# PG03_SHEET1.net
KiCad netlist of a schematic drawn in Altium Designer
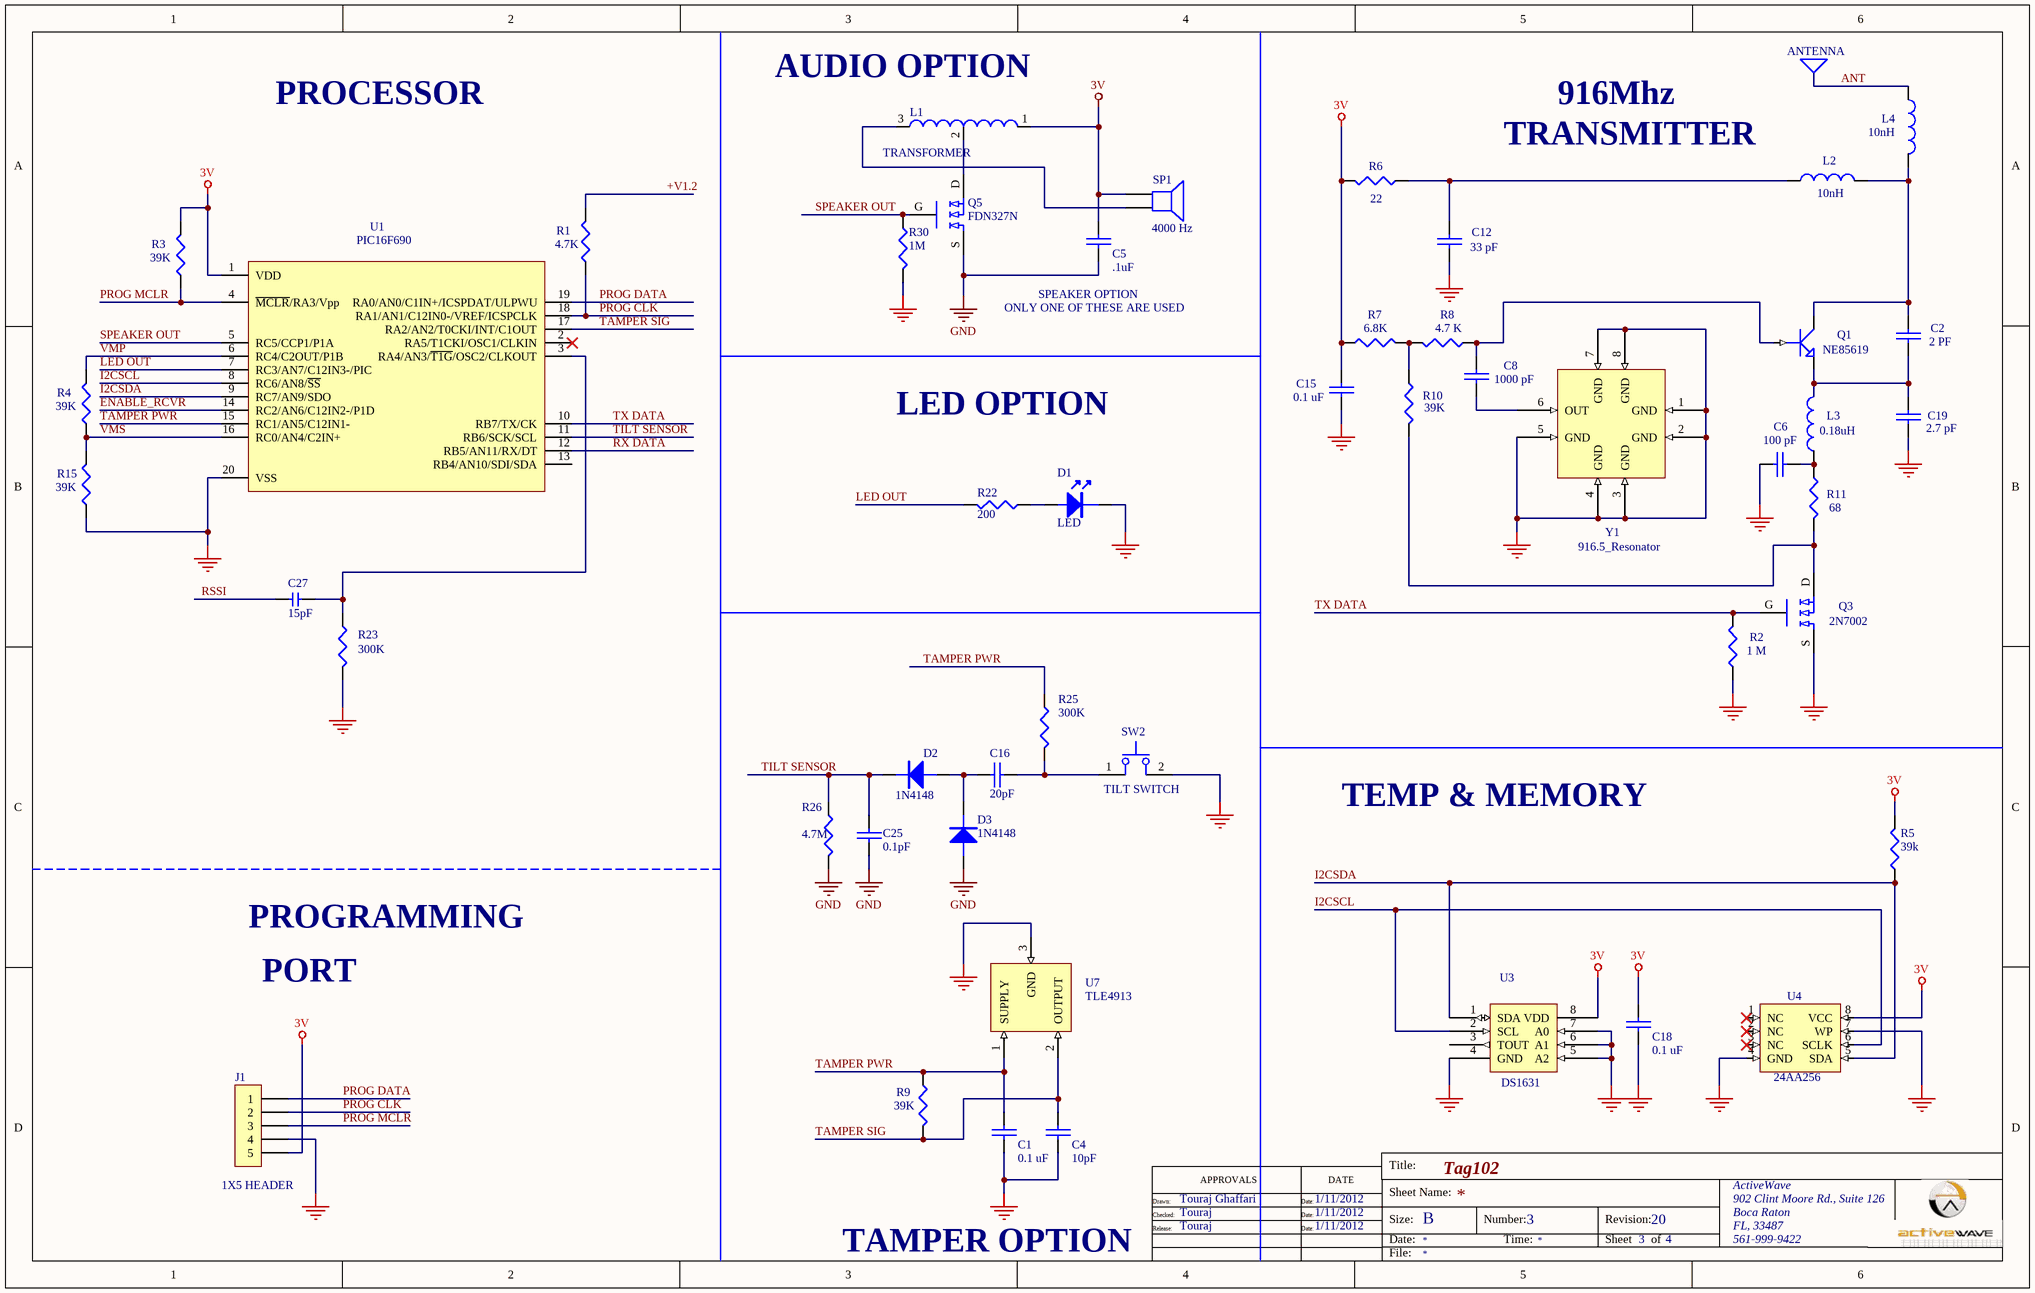
[diagram p0: PG03 SHEET1.schdoc]

(export (version "E")
  (design (tool "Eeschema 10.0.6"))
  (components
    (comp (ref "C1")
      (value "0.1 uF")
      (footprint "0603")
      (description "Capacitor")
      (libsource (lib "*") (part "CAP"))
    )
    (comp (ref "C2")
      (value "2 PF")
      (footprint "0603")
      (description "Capacitor")
      (libsource (lib "*") (part "CAP"))
    )
    (comp (ref "C4")
      (value "10pF")
      (footprint "0603")
      (description "Capacitor")
      (libsource (lib "*") (part "CAP"))
    )
    (comp (ref "C5")
      (value ".1uF")
      (footprint "0603")
      (description "Capacitor")
      (libsource (lib "ActiveWave MasterLib") (part "CAP-0603"))
    )
    (comp (ref "C6")
      (value "100 pF")
      (footprint "0603")
      (description "Capacitor")
      (libsource (lib "*") (part "CAP"))
    )
    (comp (ref "C8")
      (value "1000 pF")
      (footprint "0603")
      (description "Capacitor")
      (libsource (lib "*") (part "CAP"))
    )
    (comp (ref "C12")
      (value "33 pF")
      (footprint "0603")
      (description "Capacitor")
      (libsource (lib "*") (part "CAP"))
    )
    (comp (ref "C15")
      (value "0.1 uF")
      (footprint "0603")
      (description "Capacitor")
      (libsource (lib "*") (part "CAP"))
    )
    (comp (ref "C16")
      (value "20pF")
      (footprint "0603")
      (description "Capacitor")
      (libsource (lib "*") (part "CAP"))
    )
    (comp (ref "C18")
      (value "0.1 uF")
      (footprint "0603")
      (description "Capacitor")
      (libsource (lib "*") (part "CAP"))
    )
    (comp (ref "C19")
      (value "2.7 pF")
      (footprint "0603")
      (description "Capacitor")
      (libsource (lib "*") (part "CAP"))
    )
    (comp (ref "C25")
      (value "0.1pF")
      (footprint "0603")
      (description "Capacitor")
      (libsource (lib "*") (part "CAP"))
    )
    (comp (ref "C27") (value "15pF") (footprint "0603") (libsource (lib "*") (part "C")))
    (comp (ref "D1") (value "LED") (footprint "LED STANLEY H_1105W") (libsource (lib "*") (part "LED")))
    (comp (ref "D2")
      (value "1N4148")
      (footprint "sod123_021405")
      (description "Diode")
      (libsource (lib "*") (part "DIODE"))
    )
    (comp (ref "D3")
      (value "1N4148")
      (footprint "sod123_021405")
      (description "Diode")
      (libsource (lib "*") (part "DIODE"))
    )
    (comp (ref "J1")
      (value "1X5 HEADER")
      (footprint "1X5 HEADER")
      (description "Connector")
      (libsource (lib "*") (part "CON5"))
    )
    (comp (ref "L1")
      (value "TRANSFORMER")
      (footprint "COIL_6mmx6mm_011012")
      (libsource (lib "ActiveWave MasterLib") (part "INDUCTOR_V2"))
    )
    (comp (ref "L2") (value "10nH") (footprint "0603") (libsource (lib "*") (part "INDUCTOR")))
    (comp (ref "L3") (value "0.18uH") (footprint "0603") (libsource (lib "*") (part "INDUCTOR")))
    (comp (ref "L4") (value "10nH") (footprint "0603") (libsource (lib "*") (part "INDUCTOR")))
    (comp (ref "Q1")
      (value "NE85619")
      (footprint "3 PIN ULTRA SUPER MINI MOLD")
      (description "NPN Transistor")
      (libsource (lib "*") (part "NPN1"))
    )
    (comp (ref "Q3") (value "2N7002") (libsource (lib "*") (part "FET 2")))
    (comp (ref "Q5")
      (value "FDN327N")
      (footprint "SOT23 FET")
      (description "20V N-Channel MOSFET")
      (fields (field (name "MANUFACTURER") "FAIRCHILD"))
      (libsource (lib "ActiveWave MasterLib") (part "FDN327N"))
    )
    (comp (ref "R1") (value "4.7K") (footprint "0603") (libsource (lib "*") (part "RESISTOR")))
    (comp (ref "R2") (value "1 M") (footprint "0603") (libsource (lib "*") (part "RESISTOR")))
    (comp (ref "R3") (value "39K") (footprint "0603") (libsource (lib "*") (part "RESISTOR")))
    (comp (ref "R4") (value "39K") (footprint "0603") (libsource (lib "*") (part "RESISTOR")))
    (comp (ref "R5") (value "39k") (footprint "0603") (libsource (lib "*") (part "RESISTOR")))
    (comp (ref "R6") (value "22") (footprint "0603") (libsource (lib "*") (part "RESISTOR")))
    (comp (ref "R7") (value "6.8K") (footprint "0603") (libsource (lib "*") (part "RESISTOR")))
    (comp (ref "R8") (value "4.7 K") (footprint "0603") (libsource (lib "*") (part "RESISTOR")))
    (comp (ref "R9") (value "39K") (footprint "0603") (libsource (lib "*") (part "RESISTOR")))
    (comp (ref "R10") (value "39K") (footprint "0603") (libsource (lib "*") (part "RESISTOR")))
    (comp (ref "R11") (value "68") (footprint "0603") (libsource (lib "*") (part "RES1")))
    (comp (ref "R15") (value "39K") (footprint "0603") (libsource (lib "*") (part "RESISTOR")))
    (comp (ref "R22") (value "200") (footprint "0603") (libsource (lib "*") (part "RES1")))
    (comp (ref "R23") (value "300K") (footprint "0603") (libsource (lib "*") (part "RESISTOR")))
    (comp (ref "R25") (value "300K") (footprint "0603") (libsource (lib "*") (part "RESISTOR")))
    (comp (ref "R26") (value "4.7M") (footprint "0603") (libsource (lib "*") (part "RESISTOR")))
    (comp (ref "R30")
      (value "1M")
      (footprint "0603")
      (libsource (lib "ActiveWave MasterLib") (part "RES-0402"))
    )
    (comp (ref "SP1")
      (value "4000 Hz")
      (footprint "SPEAKER 12mmx12mm_011012")
      (description "Surface Mount Transducer")
      (fields (field (name "MANUFACTURER") "PUI Audio"))
      (libsource (lib "ActiveWave MasterLib") (part "SMT-1028-S-R"))
    )
    (comp (ref "SW2")
      (value "TILT SWITCH")
      (footprint "SQ-SEN-200")
      (libsource (lib "Common") (part "SWITCH PB"))
    )
    (comp (ref "U1") (value "PIC16F690") (libsource (lib "*") (part "PIC16F690")))
    (comp (ref "U3") (value "DS1631") (footprint "SO8 SMALL") (libsource (lib "*") (part "DS1631")))
    (comp (ref "U4") (value "24AA256") (footprint "SO8") (libsource (lib "*") (part "24AA256")))
    (comp (ref "U7") (value "TLE4913") (footprint "SOT23W") (libsource (lib "*") (part "HALL EFFECT SWITCH")))
    (comp (ref "Y1")
      (value "916.5_Resonator")
      (footprint "RESONATOR")
      (libsource (lib "*") (part "RESONATOR"))
    )
  )
  (nets
    (net (code "1") (name "/+V1.2") (class "Default")
      (node (ref "R1") (pin "2") (pinfunction "2_2") (pintype "passive"))
    )
    (net (code "2") (name "/ANT") (class "Default")
      (node (ref "L4") (pin "1") (pinfunction "1_1") (pintype "passive"))
    )
    (net (code "3") (name "/ENABLE_RCVR") (class "Default")
      (node (ref "U1") (pin "14") (pinfunction "RC2/AN6/C12IN2-/P1D_14") (pintype "passive"))
    )
    (net (code "4") (name "/I2CSCL") (class "Default")
      (node (ref "U1") (pin "8") (pinfunction "RC6/AN8/~{SS}_8") (pintype "passive"))
      (node (ref "U3") (pin "2") (pinfunction "SCL_2") (pintype "input"))
      (node (ref "U4") (pin "6") (pinfunction "SCLK_6") (pintype "input"))
    )
    (net (code "5") (name "/I2CSDA") (class "Default")
      (node (ref "R5") (pin "1") (pinfunction "1_1") (pintype "passive"))
      (node (ref "U1") (pin "9") (pinfunction "RC7/AN9/SDO_9") (pintype "passive"))
      (node (ref "U3") (pin "1") (pinfunction "SDA_1") (pintype "bidirectional"))
      (node (ref "U4") (pin "5") (pinfunction "SDA_5") (pintype "input"))
    )
    (net (code "6") (name "/LED OUT") (class "Default")
      (node (ref "R22") (pin "2") (pinfunction "2_2") (pintype "passive"))
      (node (ref "U1") (pin "7") (pinfunction "RC3/AN7/C12IN3-/PIC_7") (pintype "passive"))
    )
    (net (code "7") (name "/PROG CLK") (class "Default")
      (node (ref "J1") (pin "2") (pinfunction "2_2") (pintype "passive"))
      (node (ref "R1") (pin "1") (pinfunction "1_1") (pintype "passive"))
      (node (ref "U1") (pin "18") (pinfunction "RA1/AN1/C12IN0-/VREF/ICSPCLK_18") (pintype "passive"))
    )
    (net (code "8") (name "/PROG DATA") (class "Default")
      (node (ref "J1") (pin "1") (pinfunction "1_1") (pintype "passive"))
      (node (ref "U1") (pin "19") (pinfunction "RA0/AN0/C1IN+/ICSPDAT/ULPWU_19") (pintype "passive"))
    )
    (net (code "9") (name "/PROG MCLR") (class "Default")
      (node (ref "J1") (pin "3") (pinfunction "3_3") (pintype "passive"))
      (node (ref "R3") (pin "1") (pinfunction "1_1") (pintype "passive"))
      (node (ref "U1") (pin "4") (pinfunction "~{MCLR}/RA3/Vpp_4") (pintype "passive"))
    )
    (net (code "10") (name "/RSSI") (class "Default")
      (node (ref "C27") (pin "2") (pinfunction "2_2") (pintype "passive"))
    )
    (net (code "11") (name "/RX DATA") (class "Default")
      (node (ref "U1") (pin "12") (pinfunction "RB5/AN11/RX/DT_12") (pintype "passive"))
    )
    (net (code "12") (name "/SPEAKER OUT") (class "Default")
      (node (ref "Q5") (pin "G") (pinfunction "G_G") (pintype "passive"))
      (node (ref "R30") (pin "1") (pinfunction "1_1") (pintype "passive"))
      (node (ref "U1") (pin "5") (pinfunction "RC5/CCP1/P1A_5") (pintype "passive"))
    )
    (net (code "13") (name "/TAMPER PWR") (class "Default")
      (node (ref "C1") (pin "1") (pinfunction "1_1") (pintype "passive"))
      (node (ref "R25") (pin "1") (pinfunction "1_1") (pintype "passive"))
      (node (ref "R9") (pin "1") (pinfunction "1_1") (pintype "passive"))
      (node (ref "U1") (pin "15") (pinfunction "RC1/AN5/C12IN1-_15") (pintype "passive"))
      (node (ref "U7") (pin "1") (pinfunction "SUPPLY_1") (pintype "input"))
    )
    (net (code "14") (name "/TAMPER SIG") (class "Default")
      (node (ref "C4") (pin "1") (pinfunction "1_1") (pintype "passive"))
      (node (ref "R9") (pin "2") (pinfunction "2_2") (pintype "passive"))
      (node (ref "U1") (pin "17") (pinfunction "RA2/AN2/T0CKI/INT/C1OUT_17") (pintype "passive"))
      (node (ref "U7") (pin "2") (pinfunction "OUTPUT_2") (pintype "input"))
    )
    (net (code "15") (name "/TILT SENSOR") (class "Default")
      (node (ref "C25") (pin "1") (pinfunction "1_1") (pintype "passive"))
      (node (ref "D2") (pin "K") (pinfunction "K_K") (pintype "passive"))
      (node (ref "R26") (pin "1") (pinfunction "1_1") (pintype "passive"))
      (node (ref "U1") (pin "11") (pinfunction "RB6/SCK/SCL_11") (pintype "passive"))
    )
    (net (code "16") (name "/TX DATA") (class "Default")
      (node (ref "Q3") (pin "G") (pinfunction "G_G") (pintype "passive"))
      (node (ref "R2") (pin "2") (pinfunction "2_2") (pintype "passive"))
      (node (ref "U1") (pin "10") (pinfunction "RB7/TX/CK_10") (pintype "passive"))
    )
    (net (code "17") (name "/VMP") (class "Default")
      (node (ref "R4") (pin "2") (pinfunction "2_2") (pintype "passive"))
      (node (ref "U1") (pin "6") (pinfunction "RC4/C2OUT/P1B_6") (pintype "passive"))
    )
    (net (code "18") (name "/VMS") (class "Default")
      (node (ref "R15") (pin "2") (pinfunction "2_2") (pintype "passive"))
      (node (ref "R4") (pin "1") (pinfunction "1_1") (pintype "passive"))
      (node (ref "U1") (pin "16") (pinfunction "RC0/AN4/C2IN+_16") (pintype "passive"))
    )
    (net (code "19") (name "3V") (class "Default")
      (node (ref "C15") (pin "1") (pinfunction "1_1") (pintype "passive"))
      (node (ref "C18") (pin "1") (pinfunction "1_1") (pintype "passive"))
      (node (ref "C5") (pin "1") (pinfunction "1_1") (pintype "passive"))
      (node (ref "J1") (pin "5") (pinfunction "5_5") (pintype "passive"))
      (node (ref "L1") (pin "1") (pinfunction "1_1") (pintype "passive"))
      (node (ref "R3") (pin "2") (pinfunction "2_2") (pintype "passive"))
      (node (ref "R5") (pin "2") (pinfunction "2_2") (pintype "passive"))
      (node (ref "R6") (pin "2") (pinfunction "2_2") (pintype "passive"))
      (node (ref "R7") (pin "1") (pinfunction "1_1") (pintype "passive"))
      (node (ref "SP1") (pin "1") (pinfunction "1_1") (pintype "passive"))
      (node (ref "U1") (pin "1") (pinfunction "VDD_1") (pintype "passive"))
      (node (ref "U3") (pin "8") (pinfunction "VDD_8") (pintype "power_in"))
      (node (ref "U4") (pin "8") (pinfunction "VCC_8") (pintype "input"))
    )
    (net (code "20") (name "GND") (class "Default")
      (node (ref "C1") (pin "2") (pinfunction "2_2") (pintype "passive"))
      (node (ref "C12") (pin "2") (pinfunction "2_2") (pintype "passive"))
      (node (ref "C15") (pin "2") (pinfunction "2_2") (pintype "passive"))
      (node (ref "C18") (pin "2") (pinfunction "2_2") (pintype "passive"))
      (node (ref "C19") (pin "2") (pinfunction "2_2") (pintype "passive"))
      (node (ref "C25") (pin "2") (pinfunction "2_2") (pintype "passive"))
      (node (ref "C4") (pin "2") (pinfunction "2_2") (pintype "passive"))
      (node (ref "C5") (pin "2") (pinfunction "2_2") (pintype "passive"))
      (node (ref "C6") (pin "1") (pinfunction "1_1") (pintype "passive"))
      (node (ref "D1") (pin "K") (pinfunction "K_K") (pintype "passive"))
      (node (ref "D3") (pin "A") (pinfunction "A_A") (pintype "passive"))
      (node (ref "J1") (pin "4") (pinfunction "4_4") (pintype "passive"))
      (node (ref "Q3") (pin "S") (pinfunction "S_S") (pintype "passive"))
      (node (ref "Q5") (pin "S") (pinfunction "S_S") (pintype "passive"))
      (node (ref "R15") (pin "1") (pinfunction "1_1") (pintype "passive"))
      (node (ref "R2") (pin "1") (pinfunction "1_1") (pintype "passive"))
      (node (ref "R23") (pin "2") (pinfunction "2_2") (pintype "passive"))
      (node (ref "R26") (pin "2") (pinfunction "2_2") (pintype "passive"))
      (node (ref "R30") (pin "2") (pinfunction "2_2") (pintype "passive"))
      (node (ref "SW2") (pin "2") (pinfunction "2_2") (pintype "passive"))
      (node (ref "U1") (pin "20") (pinfunction "VSS_20") (pintype "passive"))
      (node (ref "U3") (pin "4") (pinfunction "GND_4") (pintype "power_in"))
      (node (ref "U3") (pin "5") (pinfunction "A2_5") (pintype "input"))
      (node (ref "U3") (pin "6") (pinfunction "A1_6") (pintype "input"))
      (node (ref "U3") (pin "7") (pinfunction "A0_7") (pintype "input"))
      (node (ref "U4") (pin "4") (pinfunction "GND_4") (pintype "input"))
      (node (ref "U4") (pin "7") (pinfunction "WP_7") (pintype "input"))
      (node (ref "U7") (pin "3") (pinfunction "GND_3") (pintype "input"))
      (node (ref "Y1") (pin "1") (pinfunction "GND_1") (pintype "input"))
      (node (ref "Y1") (pin "2") (pinfunction "GND_2") (pintype "input"))
      (node (ref "Y1") (pin "3") (pinfunction "GND_3") (pintype "input"))
      (node (ref "Y1") (pin "4") (pinfunction "GND_4") (pintype "input"))
      (node (ref "Y1") (pin "5") (pinfunction "GND_5") (pintype "input"))
      (node (ref "Y1") (pin "7") (pinfunction "GND_7") (pintype "input"))
      (node (ref "Y1") (pin "8") (pinfunction "GND_8") (pintype "input"))
    )
    (net (code "21") (name "Net-(C2-Pad1)") (class "Default")
      (node (ref "C2") (pin "1") (pinfunction "1_1") (pintype "passive"))
      (node (ref "L2") (pin "2") (pinfunction "2_2") (pintype "passive"))
      (node (ref "L4") (pin "2") (pinfunction "2_2") (pintype "passive"))
      (node (ref "Q1") (pin "C") (pinfunction "C_C") (pintype "passive"))
    )
    (net (code "22") (name "Net-(C6-Pad2)") (class "Default")
      (node (ref "C6") (pin "2") (pinfunction "2_2") (pintype "passive"))
      (node (ref "L3") (pin "1") (pinfunction "1_1") (pintype "passive"))
      (node (ref "R11") (pin "1") (pinfunction "1_1") (pintype "passive"))
    )
    (net (code "23") (name "Net-(C8-Pad1)") (class "Default")
      (node (ref "C8") (pin "1") (pinfunction "1_1") (pintype "passive"))
      (node (ref "Q1") (pin "B") (pinfunction "B_B") (pintype "input"))
      (node (ref "R8") (pin "1") (pinfunction "1_1") (pintype "passive"))
    )
    (net (code "24") (name "Net-(C12-Pad1)") (class "Default")
      (node (ref "C12") (pin "1") (pinfunction "1_1") (pintype "passive"))
      (node (ref "L2") (pin "1") (pinfunction "1_1") (pintype "passive"))
      (node (ref "R6") (pin "1") (pinfunction "1_1") (pintype "passive"))
    )
    (net (code "25") (name "Net-(C16-Pad1)") (class "Default")
      (node (ref "C16") (pin "1") (pinfunction "1_1") (pintype "passive"))
      (node (ref "D2") (pin "A") (pinfunction "A_A") (pintype "passive"))
      (node (ref "D3") (pin "K") (pinfunction "K_K") (pintype "passive"))
    )
    (net (code "26") (name "Net-(C16-Pad2)") (class "Default")
      (node (ref "C16") (pin "2") (pinfunction "2_2") (pintype "passive"))
      (node (ref "R25") (pin "2") (pinfunction "2_2") (pintype "passive"))
      (node (ref "SW2") (pin "1") (pinfunction "1_1") (pintype "passive"))
    )
    (net (code "27") (name "Net-(C19-Pad1)") (class "Default")
      (node (ref "C19") (pin "1") (pinfunction "1_1") (pintype "passive"))
      (node (ref "C2") (pin "2") (pinfunction "2_2") (pintype "passive"))
      (node (ref "L3") (pin "2") (pinfunction "2_2") (pintype "passive"))
      (node (ref "Q1") (pin "E") (pinfunction "E_E") (pintype "passive"))
    )
    (net (code "28") (name "Net-(D1-PadA)") (class "Default")
      (node (ref "D1") (pin "A") (pinfunction "A_A") (pintype "passive"))
      (node (ref "R22") (pin "1") (pinfunction "1_1") (pintype "passive"))
    )
    (net (code "29") (name "Net-(L1-Pad2)") (class "Default")
      (node (ref "L1") (pin "2") (pinfunction "2_2") (pintype "passive"))
      (node (ref "Q5") (pin "D") (pinfunction "D_D") (pintype "passive"))
    )
    (net (code "30") (name "Net-(L1-Pad3)") (class "Default")
      (node (ref "L1") (pin "3") (pinfunction "3_3") (pintype "passive"))
      (node (ref "SP1") (pin "2") (pinfunction "2_2") (pintype "passive"))
    )
    (net (code "31") (name "Net-(Q3-PadD)") (class "Default")
      (node (ref "Q3") (pin "D") (pinfunction "D_D") (pintype "passive"))
      (node (ref "R10") (pin "2") (pinfunction "2_2") (pintype "passive"))
      (node (ref "R11") (pin "2") (pinfunction "2_2") (pintype "passive"))
    )
    (net (code "32") (name "Net-(R10-Pad1)") (class "Default")
      (node (ref "R10") (pin "1") (pinfunction "1_1") (pintype "passive"))
      (node (ref "R7") (pin "2") (pinfunction "2_2") (pintype "passive"))
      (node (ref "R8") (pin "2") (pinfunction "2_2") (pintype "passive"))
    )
    (net (code "33") (name "Net-(U1-RA4{slash}AN3{slash}~{T1G}{slash}OSC2{slash}CLKOUT)") (class "Default")
      (node (ref "C27") (pin "1") (pinfunction "1_1") (pintype "passive"))
      (node (ref "R23") (pin "1") (pinfunction "1_1") (pintype "passive"))
      (node (ref "U1") (pin "3") (pinfunction "RA4/AN3/~{T1G}/OSC2/CLKOUT_3") (pintype "passive"))
    )
    (net (code "34") (name "Net-(Y1-OUT)") (class "Default")
      (node (ref "C8") (pin "2") (pinfunction "2_2") (pintype "passive"))
      (node (ref "Y1") (pin "6") (pinfunction "OUT_6") (pintype "input"))
    )
    (net (code "35") (name "unconnected-(U1-RA5{slash}T1CKI{slash}OSC1{slash}CLKIN-Pad2)") (class "Default")
      (node (ref "U1") (pin "2") (pinfunction "RA5/T1CKI/OSC1/CLKIN_2") (pintype "passive+no_connect"))
    )
    (net (code "36") (name "unconnected-(U1-RB4{slash}AN10{slash}SDI{slash}SDA-Pad13)") (class "Default")
      (node (ref "U1") (pin "13") (pinfunction "RB4/AN10/SDI/SDA_13") (pintype "passive"))
    )
    (net (code "37") (name "unconnected-(U3-TOUT-Pad3)") (class "Default")
      (node (ref "U3") (pin "3") (pinfunction "TOUT_3") (pintype "output"))
    )
    (net (code "38") (name "unconnected-(U4-NC-Pad1)") (class "Default")
      (node (ref "U4") (pin "1") (pinfunction "NC_1") (pintype "input+no_connect"))
    )
    (net (code "39") (name "unconnected-(U4-NC-Pad2)") (class "Default")
      (node (ref "U4") (pin "2") (pinfunction "NC_2") (pintype "input+no_connect"))
    )
    (net (code "40") (name "unconnected-(U4-NC-Pad3)") (class "Default")
      (node (ref "U4") (pin "3") (pinfunction "NC_3") (pintype "input+no_connect"))
    )
  )
)
